# Lower.net
KiCad netlist of a schematic drawn in Altium Designer
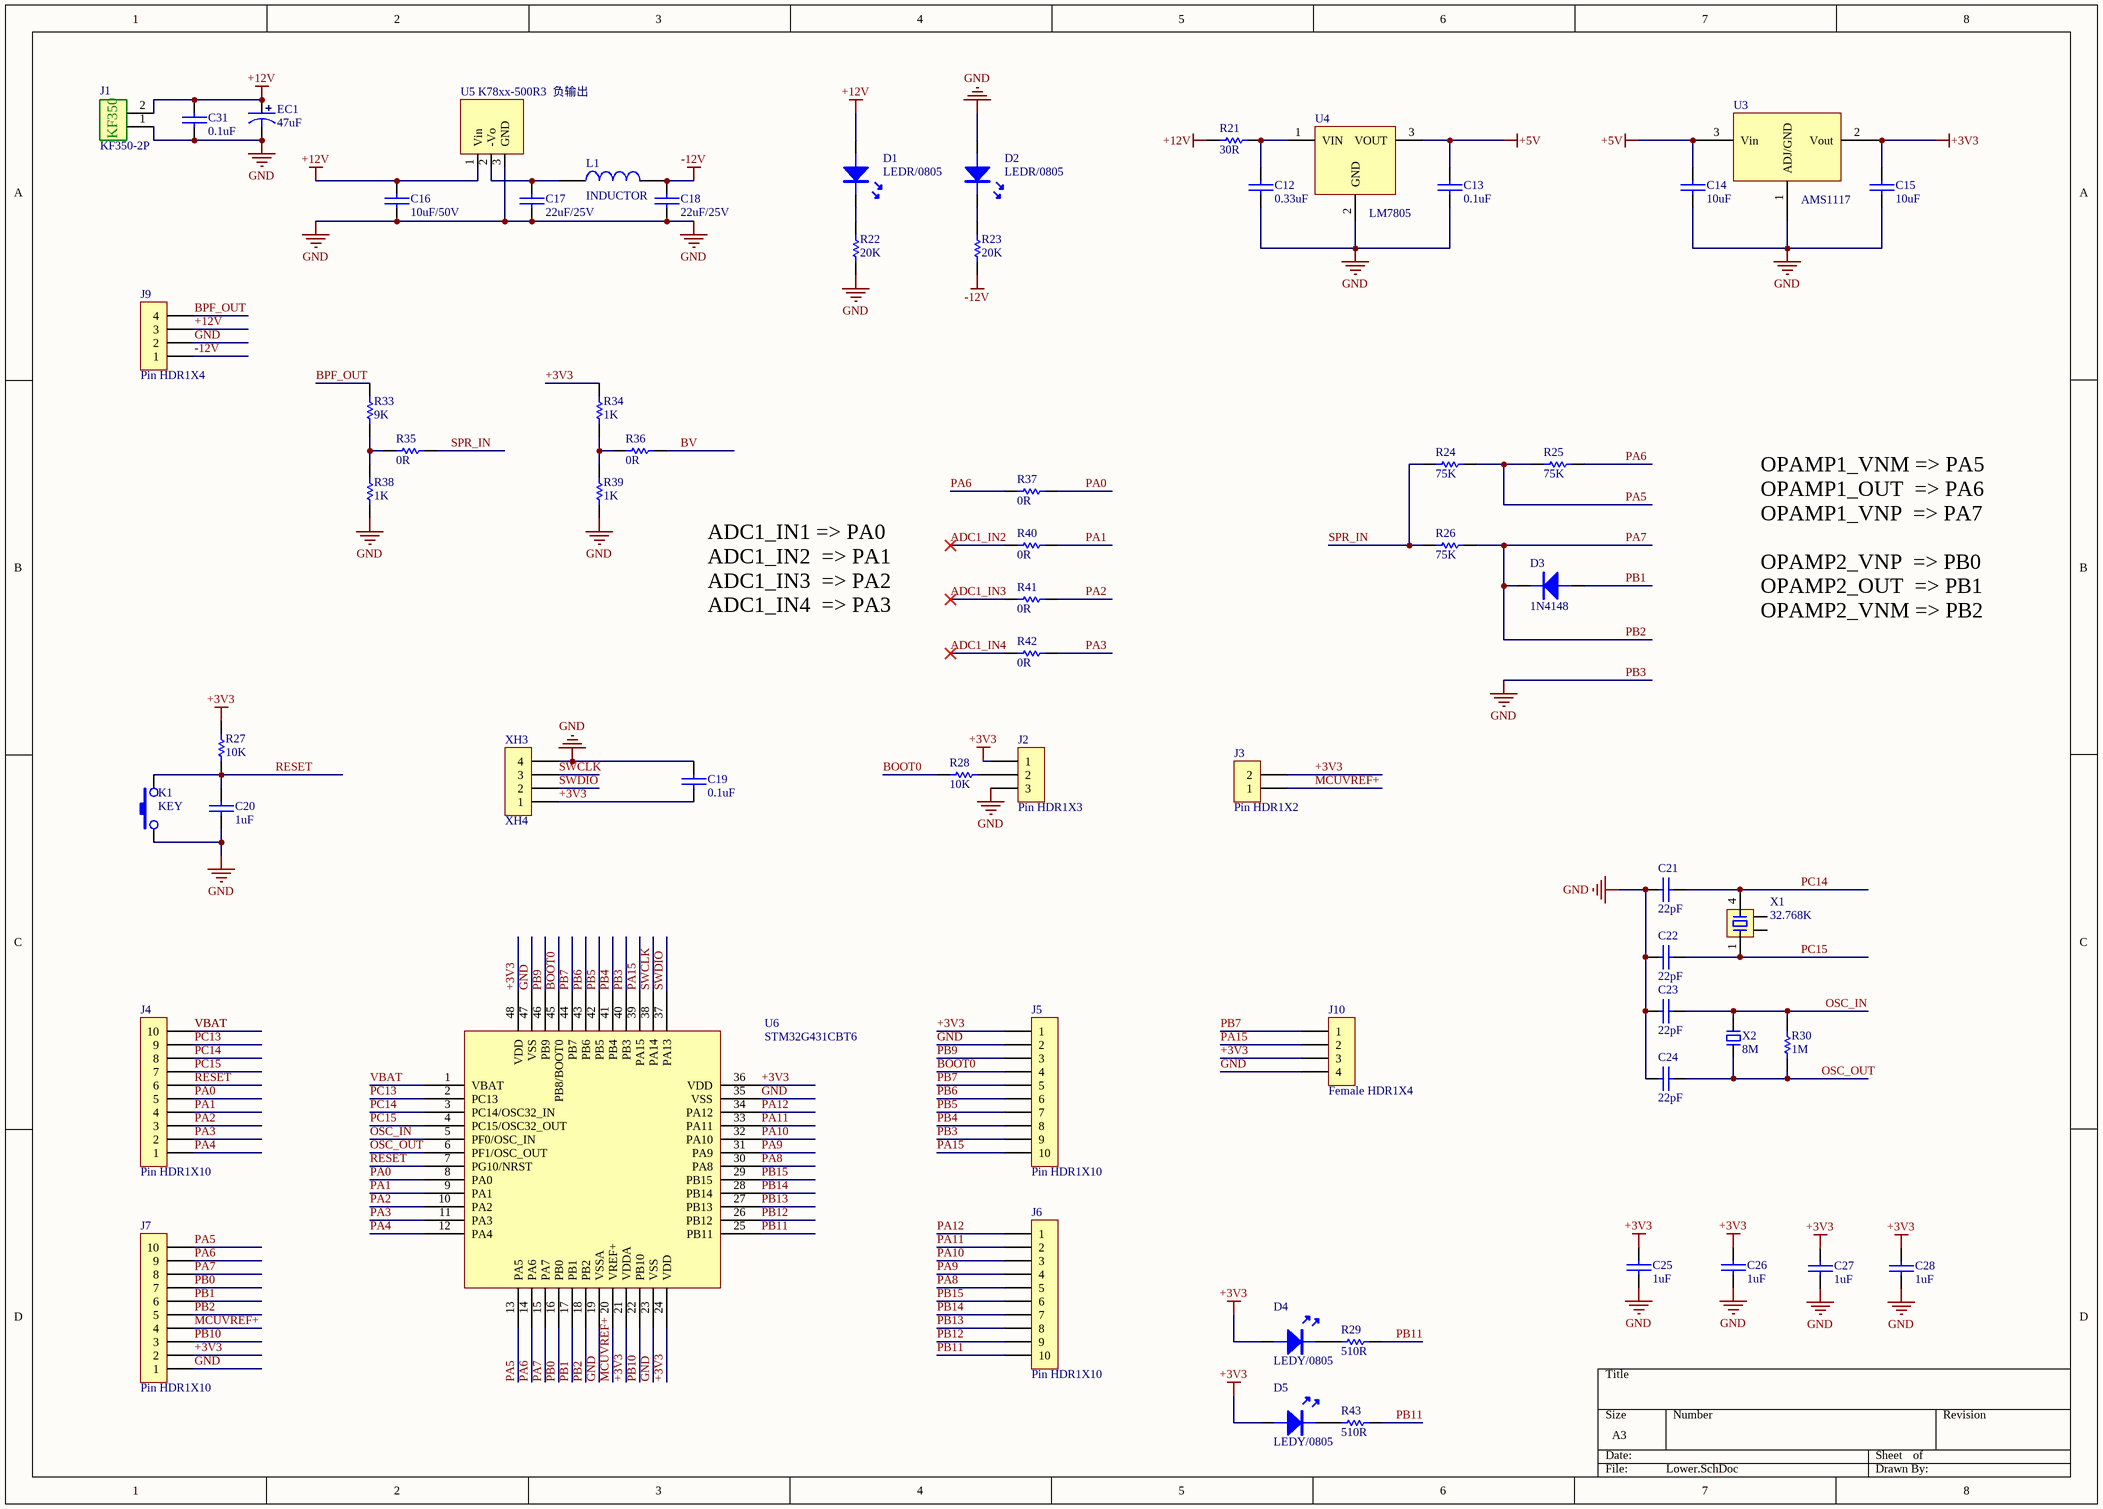
[diagram p0: Lower.SchDoc]

(export (version "E")
  (design (tool "Eeschema 10.0.6"))
  (components
    (comp (ref "C12")
      (value "0.33uF")
      (footprint "0603C")
      (description "无极性电容")
      (libsource (lib "电容") (part "CAP"))
    )
    (comp (ref "C13")
      (value "0.1uF")
      (footprint "0603C")
      (description "无极性电容")
      (libsource (lib "电容") (part "CAP"))
    )
    (comp (ref "C14")
      (value "10uF")
      (footprint "0603C")
      (description "无极性电容")
      (libsource (lib "电容") (part "CAP"))
    )
    (comp (ref "C15")
      (value "10uF")
      (footprint "0603C")
      (description "无极性电容")
      (libsource (lib "电容") (part "CAP"))
    )
    (comp (ref "C16")
      (value "10uF/50V")
      (footprint "0603C")
      (description "无极性电容")
      (libsource (lib "电容") (part "CAP"))
    )
    (comp (ref "C17")
      (value "22uF/25V")
      (footprint "0603C")
      (description "无极性电容")
      (libsource (lib "电容") (part "CAP"))
    )
    (comp (ref "C18")
      (value "22uF/25V")
      (footprint "0603C")
      (description "无极性电容")
      (libsource (lib "电容") (part "CAP"))
    )
    (comp (ref "C19")
      (value "0.1uF")
      (footprint "0603C")
      (description "无极性电容")
      (libsource (lib "电容") (part "CAP"))
    )
    (comp (ref "C20")
      (value "1uF")
      (footprint "0603C")
      (description "无极性电容")
      (libsource (lib "电容") (part "CAP"))
    )
    (comp (ref "C21")
      (value "22pF")
      (footprint "0603C")
      (description "无极性电容")
      (libsource (lib "电容") (part "CAP"))
    )
    (comp (ref "C22")
      (value "22pF")
      (footprint "0603C")
      (description "无极性电容")
      (libsource (lib "电容") (part "CAP"))
    )
    (comp (ref "C23")
      (value "22pF")
      (footprint "0603C")
      (description "无极性电容")
      (libsource (lib "电容") (part "CAP"))
    )
    (comp (ref "C24")
      (value "22pF")
      (footprint "0603C")
      (description "无极性电容")
      (libsource (lib "电容") (part "CAP"))
    )
    (comp (ref "C25")
      (value "1uF")
      (footprint "0603C")
      (description "无极性电容")
      (libsource (lib "电容") (part "CAP"))
    )
    (comp (ref "C26")
      (value "1uF")
      (footprint "0603C")
      (description "无极性电容")
      (libsource (lib "电容") (part "CAP"))
    )
    (comp (ref "C27")
      (value "1uF")
      (footprint "0603C")
      (description "无极性电容")
      (libsource (lib "电容") (part "CAP"))
    )
    (comp (ref "C28")
      (value "1uF")
      (footprint "0603C")
      (description "无极性电容")
      (libsource (lib "电容") (part "CAP"))
    )
    (comp (ref "C31")
      (value "0.1uF")
      (footprint "0603C")
      (description "无极性电容")
      (libsource (lib "电容") (part "CAP"))
    )
    (comp (ref "D1") (value "LEDR/0805") (footprint "LED5-BLUE") (libsource (lib "LED") (part "LED")))
    (comp (ref "D2") (value "LEDR/0805") (footprint "LED5-BLUE") (libsource (lib "LED") (part "LED")))
    (comp (ref "D3")
      (value "1N4148")
      (footprint "SOD-123")
      (description "普通二极管")
      (libsource (lib "二极管") (part "DIODE"))
    )
    (comp (ref "D4") (value "LEDY/0805") (footprint "LED5-BLUE") (libsource (lib "LED") (part "LED")))
    (comp (ref "D5") (value "LEDY/0805") (footprint "LED5-BLUE") (libsource (lib "LED") (part "LED")))
    (comp (ref "EC1")
      (value "47uF")
      (footprint "SMD-EC5.0X5.3X5.4")
      (description "贴片电解电容")
      (libsource (lib "电容") (part "SMD_ECAP"))
    )
    (comp (ref "J1") (value "KF350-2P") (footprint "KF350-2P") (libsource (lib "KF350") (part "KF350-2P")))
    (comp (ref "J2")
      (value "Pin HDR1X3")
      (footprint "Pin HDR1X3/2.54mm-S")
      (libsource (lib "排针") (part "Pin HDR1X3"))
    )
    (comp (ref "J3")
      (value "Pin HDR1X2")
      (footprint "Pin HDR1X2/2.54mm-S")
      (libsource (lib "排针") (part "Pin HDR1X2"))
    )
    (comp (ref "J4")
      (value "Pin HDR1X10")
      (footprint "Pin HDR1X10/2.54mm-S")
      (libsource (lib "排针") (part "Pin HDR1X10"))
    )
    (comp (ref "J5")
      (value "Pin HDR1X10")
      (footprint "Pin HDR1X10/2.54mm-S")
      (libsource (lib "") (part "Pin HDR1X10_1"))
    )
    (comp (ref "J6")
      (value "Pin HDR1X10")
      (footprint "Pin HDR1X10/2.54mm-S")
      (libsource (lib "") (part "Pin HDR1X10_1"))
    )
    (comp (ref "J7")
      (value "Pin HDR1X10")
      (footprint "Pin HDR1X10/2.54mm-S")
      (libsource (lib "排针") (part "Pin HDR1X10"))
    )
    (comp (ref "J9")
      (value "Pin HDR1X4")
      (footprint "Pin HDR1X4/2.54mm-S")
      (libsource (lib "排针") (part "Pin HDR1X4"))
    )
    (comp (ref "J10")
      (value "Female HDR1X4")
      (footprint "Fe-HDR1X4/2.54-S")
      (libsource (lib "排母") (part "Female HDR1X4"))
    )
    (comp (ref "K1") (value "KEY") (footprint "SMD-3X6X2.5") (libsource (lib "轻触开关") (part "KEY")))
    (comp (ref "L1") (value "INDUCTOR") (footprint "1210L") (libsource (lib "电感") (part "INDUCTOR")))
    (comp (ref "R21") (value "30R") (footprint "0603R") (libsource (lib "电阻") (part "RES")))
    (comp (ref "R22") (value "20K") (footprint "0603R") (libsource (lib "电阻") (part "RES")))
    (comp (ref "R23") (value "20K") (footprint "0603R") (libsource (lib "电阻") (part "RES")))
    (comp (ref "R24") (value "75K") (footprint "0603R") (libsource (lib "电阻") (part "RES")))
    (comp (ref "R25") (value "75K") (footprint "0603R") (libsource (lib "电阻") (part "RES")))
    (comp (ref "R26") (value "75K") (footprint "0603R") (libsource (lib "电阻") (part "RES")))
    (comp (ref "R27") (value "10K") (footprint "0603R") (libsource (lib "电阻") (part "RES")))
    (comp (ref "R28") (value "10K") (footprint "0603R") (libsource (lib "电阻") (part "RES")))
    (comp (ref "R29") (value "510R") (footprint "0603R") (libsource (lib "电阻") (part "RES")))
    (comp (ref "R30") (value "1M") (footprint "0603R") (libsource (lib "电阻") (part "RES")))
    (comp (ref "R33") (value "9K") (footprint "0603R") (libsource (lib "电阻") (part "RES")))
    (comp (ref "R34") (value "1K") (footprint "0603R") (libsource (lib "电阻") (part "RES")))
    (comp (ref "R35") (value "0R") (footprint "0603R") (libsource (lib "电阻") (part "RES")))
    (comp (ref "R36") (value "0R") (footprint "0603R") (libsource (lib "电阻") (part "RES")))
    (comp (ref "R37") (value "0R") (footprint "0603R") (libsource (lib "电阻") (part "RES")))
    (comp (ref "R38") (value "1K") (footprint "0603R") (libsource (lib "电阻") (part "RES")))
    (comp (ref "R39") (value "1K") (footprint "0603R") (libsource (lib "电阻") (part "RES")))
    (comp (ref "R40") (value "0R") (footprint "0603R") (libsource (lib "电阻") (part "RES")))
    (comp (ref "R41") (value "0R") (footprint "0603R") (libsource (lib "电阻") (part "RES")))
    (comp (ref "R42") (value "0R") (footprint "0603R") (libsource (lib "电阻") (part "RES")))
    (comp (ref "R43") (value "510R") (footprint "0603R") (libsource (lib "电阻") (part "RES")))
    (comp (ref "U3")
      (value "AMS1117")
      (footprint "SOT223")
      (description "三端稳压芯片")
      (libsource (lib "电源芯片") (part "AMS1117"))
    )
    (comp (ref "U4") (value "LM7805") (footprint "TO252") (libsource (lib "电源芯片") (part "LM7805")))
    (comp (ref "U5")
      (value "K78xx-500R3  负输出")
      (footprint "K78xx-500R3 负输出")
      (libsource (lib "传感器") (part "K78xx-500R3  负输出"))
    )
    (comp (ref "U6")
      (value "STM32G431CBT6")
      (footprint "LQFP48 7X7")
      (libsource (lib "STM32系列") (part "STM32G431CBT6"))
    )
    (comp (ref "X1")
      (value "32.768K")
      (footprint "OSC MC-306")
      (description "MC系列4脚晶振")
      (libsource (lib "晶振") (part "XTAL-MC-4P"))
    )
    (comp (ref "X2")
      (value "8M")
      (footprint "OSC HC-49S")
      (description "2脚无源脚晶振")
      (libsource (lib "晶振") (part "XTAL-2P"))
    )
    (comp (ref "XH3") (value "XH4") (footprint "XH4/2.54mm/180") (libsource (lib "XH，VH") (part "XH4")))
  )
  (nets
    (net (code "1") (name "+3V3") (class "Default")
      (node (ref "C15") (pin "2") (pinfunction "2_2") (pintype "passive"))
      (node (ref "C19") (pin "1") (pinfunction "1_1") (pintype "passive"))
      (node (ref "C25") (pin "2") (pinfunction "2_2") (pintype "passive"))
      (node (ref "C26") (pin "2") (pinfunction "2_2") (pintype "passive"))
      (node (ref "C27") (pin "2") (pinfunction "2_2") (pintype "passive"))
      (node (ref "C28") (pin "2") (pinfunction "2_2") (pintype "passive"))
      (node (ref "D4") (pin "A") (pinfunction "A_A") (pintype "passive"))
      (node (ref "D5") (pin "A") (pinfunction "A_A") (pintype "passive"))
      (node (ref "J10") (pin "3") (pinfunction "3_3") (pintype "passive"))
      (node (ref "J2") (pin "1") (pinfunction "1_1") (pintype "passive"))
      (node (ref "J3") (pin "2") (pinfunction "2_2") (pintype "passive"))
      (node (ref "J5") (pin "1") (pinfunction "1_1") (pintype "passive"))
      (node (ref "J7") (pin "2") (pinfunction "2_2") (pintype "passive"))
      (node (ref "R27") (pin "1") (pinfunction "1_1") (pintype "passive"))
      (node (ref "R34") (pin "2") (pinfunction "2_2") (pintype "passive"))
      (node (ref "U3") (pin "2") (pinfunction "Vout_2") (pintype "passive"))
      (node (ref "U6") (pin "21") (pinfunction "VDDA_21") (pintype "passive"))
      (node (ref "U6") (pin "24") (pinfunction "VDD_24") (pintype "passive"))
      (node (ref "U6") (pin "36") (pinfunction "VDD_36") (pintype "passive"))
      (node (ref "U6") (pin "48") (pinfunction "VDD_48") (pintype "passive"))
      (node (ref "XH3") (pin "1") (pinfunction "1_1") (pintype "passive"))
    )
    (net (code "2") (name "+5V") (class "Default")
      (node (ref "C13") (pin "2") (pinfunction "2_2") (pintype "passive"))
      (node (ref "C14") (pin "2") (pinfunction "2_2") (pintype "passive"))
      (node (ref "U3") (pin "3") (pinfunction "Vin_3") (pintype "passive"))
      (node (ref "U4") (pin "3") (pinfunction "VOUT_3") (pintype "passive"))
    )
    (net (code "3") (name "+12V") (class "Default")
      (node (ref "C16") (pin "2") (pinfunction "2_2") (pintype "passive"))
      (node (ref "C31") (pin "2") (pinfunction "2_2") (pintype "passive"))
      (node (ref "D1") (pin "A") (pinfunction "A_A") (pintype "passive"))
      (node (ref "EC1") (pin "1") (pinfunction "1_1") (pintype "passive"))
      (node (ref "J1") (pin "2") (pinfunction "2_2") (pintype "passive"))
      (node (ref "J9") (pin "3") (pinfunction "3_3") (pintype "passive"))
      (node (ref "R21") (pin "1") (pinfunction "1_1") (pintype "passive"))
      (node (ref "U5") (pin "1") (pinfunction "Vin_1") (pintype "passive"))
    )
    (net (code "4") (name "-12V") (class "Default")
      (node (ref "C18") (pin "2") (pinfunction "2_2") (pintype "passive"))
      (node (ref "J9") (pin "1") (pinfunction "1_1") (pintype "passive"))
      (node (ref "L1") (pin "2") (pinfunction "2_2") (pintype "passive"))
      (node (ref "R23") (pin "2") (pinfunction "2_2") (pintype "passive"))
    )
    (net (code "5") (name "/ADC1_IN2") (class "Default")
      (node (ref "R40") (pin "1") (pinfunction "1_1") (pintype "passive+no_connect"))
    )
    (net (code "6") (name "/ADC1_IN3") (class "Default")
      (node (ref "R41") (pin "1") (pinfunction "1_1") (pintype "passive+no_connect"))
    )
    (net (code "7") (name "/ADC1_IN4") (class "Default")
      (node (ref "R42") (pin "1") (pinfunction "1_1") (pintype "passive+no_connect"))
    )
    (net (code "8") (name "/BOOT0") (class "Default")
      (node (ref "J5") (pin "4") (pinfunction "4_4") (pintype "passive"))
      (node (ref "R28") (pin "1") (pinfunction "1_1") (pintype "passive"))
      (node (ref "U6") (pin "45") (pinfunction "PB8/BOOT0_45") (pintype "passive"))
    )
    (net (code "9") (name "/BPF_OUT") (class "Default")
      (node (ref "J9") (pin "4") (pinfunction "4_4") (pintype "passive"))
      (node (ref "R33") (pin "2") (pinfunction "2_2") (pintype "passive"))
    )
    (net (code "10") (name "/BV") (class "Default")
      (node (ref "R36") (pin "1") (pinfunction "1_1") (pintype "passive"))
    )
    (net (code "11") (name "/MCUVREF+") (class "Default")
      (node (ref "J3") (pin "1") (pinfunction "1_1") (pintype "passive"))
      (node (ref "J7") (pin "4") (pinfunction "4_4") (pintype "passive"))
      (node (ref "U6") (pin "20") (pinfunction "VREF+_20") (pintype "passive"))
    )
    (net (code "12") (name "/OSC_IN") (class "Default")
      (node (ref "C23") (pin "1") (pinfunction "1_1") (pintype "passive"))
      (node (ref "R30") (pin "2") (pinfunction "2_2") (pintype "passive"))
      (node (ref "U6") (pin "5") (pinfunction "PF0/OSC_IN_5") (pintype "passive"))
      (node (ref "X2") (pin "2") (pinfunction "2_2") (pintype "passive"))
    )
    (net (code "13") (name "/OSC_OUT") (class "Default")
      (node (ref "C24") (pin "1") (pinfunction "1_1") (pintype "passive"))
      (node (ref "R30") (pin "1") (pinfunction "1_1") (pintype "passive"))
      (node (ref "U6") (pin "6") (pinfunction "PF1/OSC_OUT_6") (pintype "passive"))
      (node (ref "X2") (pin "1") (pinfunction "1_1") (pintype "passive"))
    )
    (net (code "14") (name "/PA0") (class "Default")
      (node (ref "J4") (pin "5") (pinfunction "5_5") (pintype "passive"))
      (node (ref "R37") (pin "2") (pinfunction "2_2") (pintype "passive"))
      (node (ref "U6") (pin "8") (pinfunction "PA0_8") (pintype "passive"))
    )
    (net (code "15") (name "/PA1") (class "Default")
      (node (ref "J4") (pin "4") (pinfunction "4_4") (pintype "passive"))
      (node (ref "R40") (pin "2") (pinfunction "2_2") (pintype "passive"))
      (node (ref "U6") (pin "9") (pinfunction "PA1_9") (pintype "passive"))
    )
    (net (code "16") (name "/PA2") (class "Default")
      (node (ref "J4") (pin "3") (pinfunction "3_3") (pintype "passive"))
      (node (ref "R41") (pin "2") (pinfunction "2_2") (pintype "passive"))
      (node (ref "U6") (pin "10") (pinfunction "PA2_10") (pintype "passive"))
    )
    (net (code "17") (name "/PA3") (class "Default")
      (node (ref "J4") (pin "2") (pinfunction "2_2") (pintype "passive"))
      (node (ref "R42") (pin "2") (pinfunction "2_2") (pintype "passive"))
      (node (ref "U6") (pin "11") (pinfunction "PA3_11") (pintype "passive"))
    )
    (net (code "18") (name "/PA4") (class "Default")
      (node (ref "J4") (pin "1") (pinfunction "1_1") (pintype "passive"))
      (node (ref "U6") (pin "12") (pinfunction "PA4_12") (pintype "passive"))
    )
    (net (code "19") (name "/PA5") (class "Default")
      (node (ref "J7") (pin "10") (pinfunction "10_10") (pintype "passive"))
      (node (ref "R24") (pin "2") (pinfunction "2_2") (pintype "passive"))
      (node (ref "R25") (pin "1") (pinfunction "1_1") (pintype "passive"))
      (node (ref "U6") (pin "13") (pinfunction "PA5_13") (pintype "passive"))
    )
    (net (code "20") (name "/PA6") (class "Default")
      (node (ref "J7") (pin "9") (pinfunction "9_9") (pintype "passive"))
      (node (ref "R25") (pin "2") (pinfunction "2_2") (pintype "passive"))
      (node (ref "R37") (pin "1") (pinfunction "1_1") (pintype "passive"))
      (node (ref "U6") (pin "14") (pinfunction "PA6_14") (pintype "passive"))
    )
    (net (code "21") (name "/PA7") (class "Default")
      (node (ref "D3") (pin "K") (pinfunction "K_K") (pintype "passive"))
      (node (ref "J7") (pin "5") (pinfunction "5_5") (pintype "passive"))
      (node (ref "J7") (pin "8") (pinfunction "8_8") (pintype "passive"))
      (node (ref "R26") (pin "2") (pinfunction "2_2") (pintype "passive"))
      (node (ref "U6") (pin "15") (pinfunction "PA7_15") (pintype "passive"))
      (node (ref "U6") (pin "18") (pinfunction "PB2_18") (pintype "passive"))
    )
    (net (code "22") (name "/PA8") (class "Default")
      (node (ref "J6") (pin "5") (pinfunction "5_5") (pintype "passive"))
      (node (ref "U6") (pin "30") (pinfunction "PA8_30") (pintype "passive"))
    )
    (net (code "23") (name "/PA9") (class "Default")
      (node (ref "J6") (pin "4") (pinfunction "4_4") (pintype "passive"))
      (node (ref "U6") (pin "31") (pinfunction "PA9_31") (pintype "passive"))
    )
    (net (code "24") (name "/PA10") (class "Default")
      (node (ref "J6") (pin "3") (pinfunction "3_3") (pintype "passive"))
      (node (ref "U6") (pin "32") (pinfunction "PA10_32") (pintype "passive"))
    )
    (net (code "25") (name "/PA11") (class "Default")
      (node (ref "J6") (pin "2") (pinfunction "2_2") (pintype "passive"))
      (node (ref "U6") (pin "33") (pinfunction "PA11_33") (pintype "passive"))
    )
    (net (code "26") (name "/PA12") (class "Default")
      (node (ref "J6") (pin "1") (pinfunction "1_1") (pintype "passive"))
      (node (ref "U6") (pin "34") (pinfunction "PA12_34") (pintype "passive"))
    )
    (net (code "27") (name "/PA15") (class "Default")
      (node (ref "J10") (pin "2") (pinfunction "2_2") (pintype "passive"))
      (node (ref "J5") (pin "10") (pinfunction "10_10") (pintype "passive"))
      (node (ref "U6") (pin "39") (pinfunction "PA15_39") (pintype "passive"))
    )
    (net (code "28") (name "/PB0") (class "Default")
      (node (ref "J7") (pin "7") (pinfunction "7_7") (pintype "passive"))
      (node (ref "U6") (pin "16") (pinfunction "PB0_16") (pintype "passive"))
    )
    (net (code "29") (name "/PB1") (class "Default")
      (node (ref "D3") (pin "A") (pinfunction "A_A") (pintype "passive"))
      (node (ref "J7") (pin "6") (pinfunction "6_6") (pintype "passive"))
      (node (ref "U6") (pin "17") (pinfunction "PB1_17") (pintype "passive"))
    )
    (net (code "30") (name "/PB4") (class "Default")
      (node (ref "J5") (pin "8") (pinfunction "8_8") (pintype "passive"))
      (node (ref "U6") (pin "41") (pinfunction "PB4_41") (pintype "passive"))
    )
    (net (code "31") (name "/PB5") (class "Default")
      (node (ref "J5") (pin "7") (pinfunction "7_7") (pintype "passive"))
      (node (ref "U6") (pin "42") (pinfunction "PB5_42") (pintype "passive"))
    )
    (net (code "32") (name "/PB6") (class "Default")
      (node (ref "J5") (pin "6") (pinfunction "6_6") (pintype "passive"))
      (node (ref "U6") (pin "43") (pinfunction "PB6_43") (pintype "passive"))
    )
    (net (code "33") (name "/PB7") (class "Default")
      (node (ref "J10") (pin "1") (pinfunction "1_1") (pintype "passive"))
      (node (ref "J5") (pin "5") (pinfunction "5_5") (pintype "passive"))
      (node (ref "U6") (pin "44") (pinfunction "PB7_44") (pintype "passive"))
    )
    (net (code "34") (name "/PB9") (class "Default")
      (node (ref "J5") (pin "3") (pinfunction "3_3") (pintype "passive"))
      (node (ref "U6") (pin "46") (pinfunction "PB9_46") (pintype "passive"))
    )
    (net (code "35") (name "/PB10") (class "Default")
      (node (ref "J7") (pin "3") (pinfunction "3_3") (pintype "passive"))
      (node (ref "U6") (pin "22") (pinfunction "PB10_22") (pintype "passive"))
    )
    (net (code "36") (name "/PB11") (class "Default")
      (node (ref "J6") (pin "10") (pinfunction "10_10") (pintype "passive"))
      (node (ref "R29") (pin "2") (pinfunction "2_2") (pintype "passive"))
      (node (ref "R43") (pin "2") (pinfunction "2_2") (pintype "passive"))
      (node (ref "U6") (pin "25") (pinfunction "PB11_25") (pintype "passive"))
    )
    (net (code "37") (name "/PB12") (class "Default")
      (node (ref "J6") (pin "9") (pinfunction "9_9") (pintype "passive"))
      (node (ref "U6") (pin "26") (pinfunction "PB12_26") (pintype "passive"))
    )
    (net (code "38") (name "/PB13") (class "Default")
      (node (ref "J6") (pin "8") (pinfunction "8_8") (pintype "passive"))
      (node (ref "U6") (pin "27") (pinfunction "PB13_27") (pintype "passive"))
    )
    (net (code "39") (name "/PB14") (class "Default")
      (node (ref "J6") (pin "7") (pinfunction "7_7") (pintype "passive"))
      (node (ref "U6") (pin "28") (pinfunction "PB14_28") (pintype "passive"))
    )
    (net (code "40") (name "/PB15") (class "Default")
      (node (ref "J6") (pin "6") (pinfunction "6_6") (pintype "passive"))
      (node (ref "U6") (pin "29") (pinfunction "PB15_29") (pintype "passive"))
    )
    (net (code "41") (name "/PC13") (class "Default")
      (node (ref "J4") (pin "9") (pinfunction "9_9") (pintype "passive"))
      (node (ref "U6") (pin "2") (pinfunction "PC13_2") (pintype "passive"))
    )
    (net (code "42") (name "/PC14") (class "Default")
      (node (ref "C21") (pin "1") (pinfunction "1_1") (pintype "passive"))
      (node (ref "J4") (pin "8") (pinfunction "8_8") (pintype "passive"))
      (node (ref "U6") (pin "3") (pinfunction "PC14/OSC32_IN_3") (pintype "passive"))
      (node (ref "X1") (pin "4") (pinfunction "4_4") (pintype "passive"))
    )
    (net (code "43") (name "/PC15") (class "Default")
      (node (ref "C22") (pin "1") (pinfunction "1_1") (pintype "passive"))
      (node (ref "J4") (pin "7") (pinfunction "7_7") (pintype "passive"))
      (node (ref "U6") (pin "4") (pinfunction "PC15/OSC32_OUT_4") (pintype "passive"))
      (node (ref "X1") (pin "1") (pinfunction "1_1") (pintype "passive"))
    )
    (net (code "44") (name "/RESET") (class "Default")
      (node (ref "C20") (pin "2") (pinfunction "2_2") (pintype "passive"))
      (node (ref "J4") (pin "6") (pinfunction "6_6") (pintype "passive"))
      (node (ref "K1") (pin "3") (pinfunction "3_3") (pintype "passive"))
      (node (ref "R27") (pin "2") (pinfunction "2_2") (pintype "passive"))
      (node (ref "U6") (pin "7") (pinfunction "PG10/NRST_7") (pintype "passive"))
    )
    (net (code "45") (name "/SPR_IN") (class "Default")
      (node (ref "R24") (pin "1") (pinfunction "1_1") (pintype "passive"))
      (node (ref "R26") (pin "1") (pinfunction "1_1") (pintype "passive"))
      (node (ref "R35") (pin "1") (pinfunction "1_1") (pintype "passive"))
    )
    (net (code "46") (name "/SWCLK") (class "Default")
      (node (ref "U6") (pin "38") (pinfunction "PA14_38") (pintype "passive"))
      (node (ref "XH3") (pin "3") (pinfunction "3_3") (pintype "passive"))
    )
    (net (code "47") (name "/SWDIO") (class "Default")
      (node (ref "U6") (pin "37") (pinfunction "PA13_37") (pintype "passive"))
      (node (ref "XH3") (pin "2") (pinfunction "2_2") (pintype "passive"))
    )
    (net (code "48") (name "/VBAT") (class "Default")
      (node (ref "J4") (pin "10") (pinfunction "10_10") (pintype "passive"))
      (node (ref "U6") (pin "1") (pinfunction "VBAT_1") (pintype "passive"))
    )
    (net (code "49") (name "GND") (class "Default")
      (node (ref "C12") (pin "1") (pinfunction "1_1") (pintype "passive"))
      (node (ref "C13") (pin "1") (pinfunction "1_1") (pintype "passive"))
      (node (ref "C14") (pin "1") (pinfunction "1_1") (pintype "passive"))
      (node (ref "C15") (pin "1") (pinfunction "1_1") (pintype "passive"))
      (node (ref "C16") (pin "1") (pinfunction "1_1") (pintype "passive"))
      (node (ref "C17") (pin "1") (pinfunction "1_1") (pintype "passive"))
      (node (ref "C18") (pin "1") (pinfunction "1_1") (pintype "passive"))
      (node (ref "C19") (pin "2") (pinfunction "2_2") (pintype "passive"))
      (node (ref "C20") (pin "1") (pinfunction "1_1") (pintype "passive"))
      (node (ref "C21") (pin "2") (pinfunction "2_2") (pintype "passive"))
      (node (ref "C22") (pin "2") (pinfunction "2_2") (pintype "passive"))
      (node (ref "C23") (pin "2") (pinfunction "2_2") (pintype "passive"))
      (node (ref "C24") (pin "2") (pinfunction "2_2") (pintype "passive"))
      (node (ref "C25") (pin "1") (pinfunction "1_1") (pintype "passive"))
      (node (ref "C26") (pin "1") (pinfunction "1_1") (pintype "passive"))
      (node (ref "C27") (pin "1") (pinfunction "1_1") (pintype "passive"))
      (node (ref "C28") (pin "1") (pinfunction "1_1") (pintype "passive"))
      (node (ref "C31") (pin "1") (pinfunction "1_1") (pintype "passive"))
      (node (ref "D2") (pin "A") (pinfunction "A_A") (pintype "passive"))
      (node (ref "EC1") (pin "2") (pinfunction "2_2") (pintype "passive"))
      (node (ref "J1") (pin "1") (pinfunction "1_1") (pintype "passive"))
      (node (ref "J10") (pin "4") (pinfunction "4_4") (pintype "passive"))
      (node (ref "J2") (pin "3") (pinfunction "3_3") (pintype "passive"))
      (node (ref "J5") (pin "2") (pinfunction "2_2") (pintype "passive"))
      (node (ref "J5") (pin "9") (pinfunction "9_9") (pintype "passive"))
      (node (ref "J7") (pin "1") (pinfunction "1_1") (pintype "passive"))
      (node (ref "J9") (pin "2") (pinfunction "2_2") (pintype "passive"))
      (node (ref "K1") (pin "1") (pinfunction "1_1") (pintype "passive"))
      (node (ref "R22") (pin "2") (pinfunction "2_2") (pintype "passive"))
      (node (ref "R38") (pin "1") (pinfunction "1_1") (pintype "passive"))
      (node (ref "R39") (pin "1") (pinfunction "1_1") (pintype "passive"))
      (node (ref "U3") (pin "1") (pinfunction "ADJ/GND_1") (pintype "passive"))
      (node (ref "U4") (pin "2") (pinfunction "GND_2") (pintype "passive"))
      (node (ref "U5") (pin "3") (pinfunction "GND_3") (pintype "passive"))
      (node (ref "U6") (pin "19") (pinfunction "VSSA_19") (pintype "passive"))
      (node (ref "U6") (pin "23") (pinfunction "VSS_23") (pintype "passive"))
      (node (ref "U6") (pin "35") (pinfunction "VSS_35") (pintype "passive"))
      (node (ref "U6") (pin "40") (pinfunction "PB3_40") (pintype "passive"))
      (node (ref "U6") (pin "47") (pinfunction "VSS_47") (pintype "passive"))
      (node (ref "XH3") (pin "4") (pinfunction "4_4") (pintype "passive"))
    )
    (net (code "50") (name "Net-(D1-PadK)") (class "Default")
      (node (ref "D1") (pin "K") (pinfunction "K_K") (pintype "passive"))
      (node (ref "R22") (pin "1") (pinfunction "1_1") (pintype "passive"))
    )
    (net (code "51") (name "Net-(D2-PadK)") (class "Default")
      (node (ref "D2") (pin "K") (pinfunction "K_K") (pintype "passive"))
      (node (ref "R23") (pin "1") (pinfunction "1_1") (pintype "passive"))
    )
    (net (code "52") (name "Net-(D4-PadK)") (class "Default")
      (node (ref "D4") (pin "K") (pinfunction "K_K") (pintype "passive"))
      (node (ref "R29") (pin "1") (pinfunction "1_1") (pintype "passive"))
    )
    (net (code "53") (name "Net-(D5-PadK)") (class "Default")
      (node (ref "D5") (pin "K") (pinfunction "K_K") (pintype "passive"))
      (node (ref "R43") (pin "1") (pinfunction "1_1") (pintype "passive"))
    )
    (net (code "54") (name "Net-(J2-Pad2)") (class "Default")
      (node (ref "J2") (pin "2") (pinfunction "2_2") (pintype "passive"))
      (node (ref "R28") (pin "2") (pinfunction "2_2") (pintype "passive"))
    )
    (net (code "55") (name "Net-(R33-Pad1)") (class "Default")
      (node (ref "R33") (pin "1") (pinfunction "1_1") (pintype "passive"))
      (node (ref "R35") (pin "2") (pinfunction "2_2") (pintype "passive"))
      (node (ref "R38") (pin "2") (pinfunction "2_2") (pintype "passive"))
    )
    (net (code "56") (name "Net-(R34-Pad1)") (class "Default")
      (node (ref "R34") (pin "1") (pinfunction "1_1") (pintype "passive"))
      (node (ref "R36") (pin "2") (pinfunction "2_2") (pintype "passive"))
      (node (ref "R39") (pin "2") (pinfunction "2_2") (pintype "passive"))
    )
    (net (code "57") (name "Net-(U4-VIN)") (class "Default")
      (node (ref "C12") (pin "2") (pinfunction "2_2") (pintype "passive"))
      (node (ref "R21") (pin "2") (pinfunction "2_2") (pintype "passive"))
      (node (ref "U4") (pin "1") (pinfunction "VIN_1") (pintype "passive"))
    )
    (net (code "58") (name "Net-(U5--Vo)") (class "Default")
      (node (ref "C17") (pin "2") (pinfunction "2_2") (pintype "passive"))
      (node (ref "L1") (pin "1") (pinfunction "1_1") (pintype "passive"))
      (node (ref "U5") (pin "2") (pinfunction "-Vo_2") (pintype "passive"))
    )
    (net (code "59") (name "unconnected-(X1-Pad2)") (class "Default")
      (node (ref "X1") (pin "2") (pinfunction "2_2") (pintype "passive"))
    )
    (net (code "60") (name "unconnected-(X1-Pad3)") (class "Default")
      (node (ref "X1") (pin "3") (pinfunction "3_3") (pintype "passive"))
    )
  )
)
